# zeitgeist.net
KiCad netlist of a schematic drawn in EAGLE
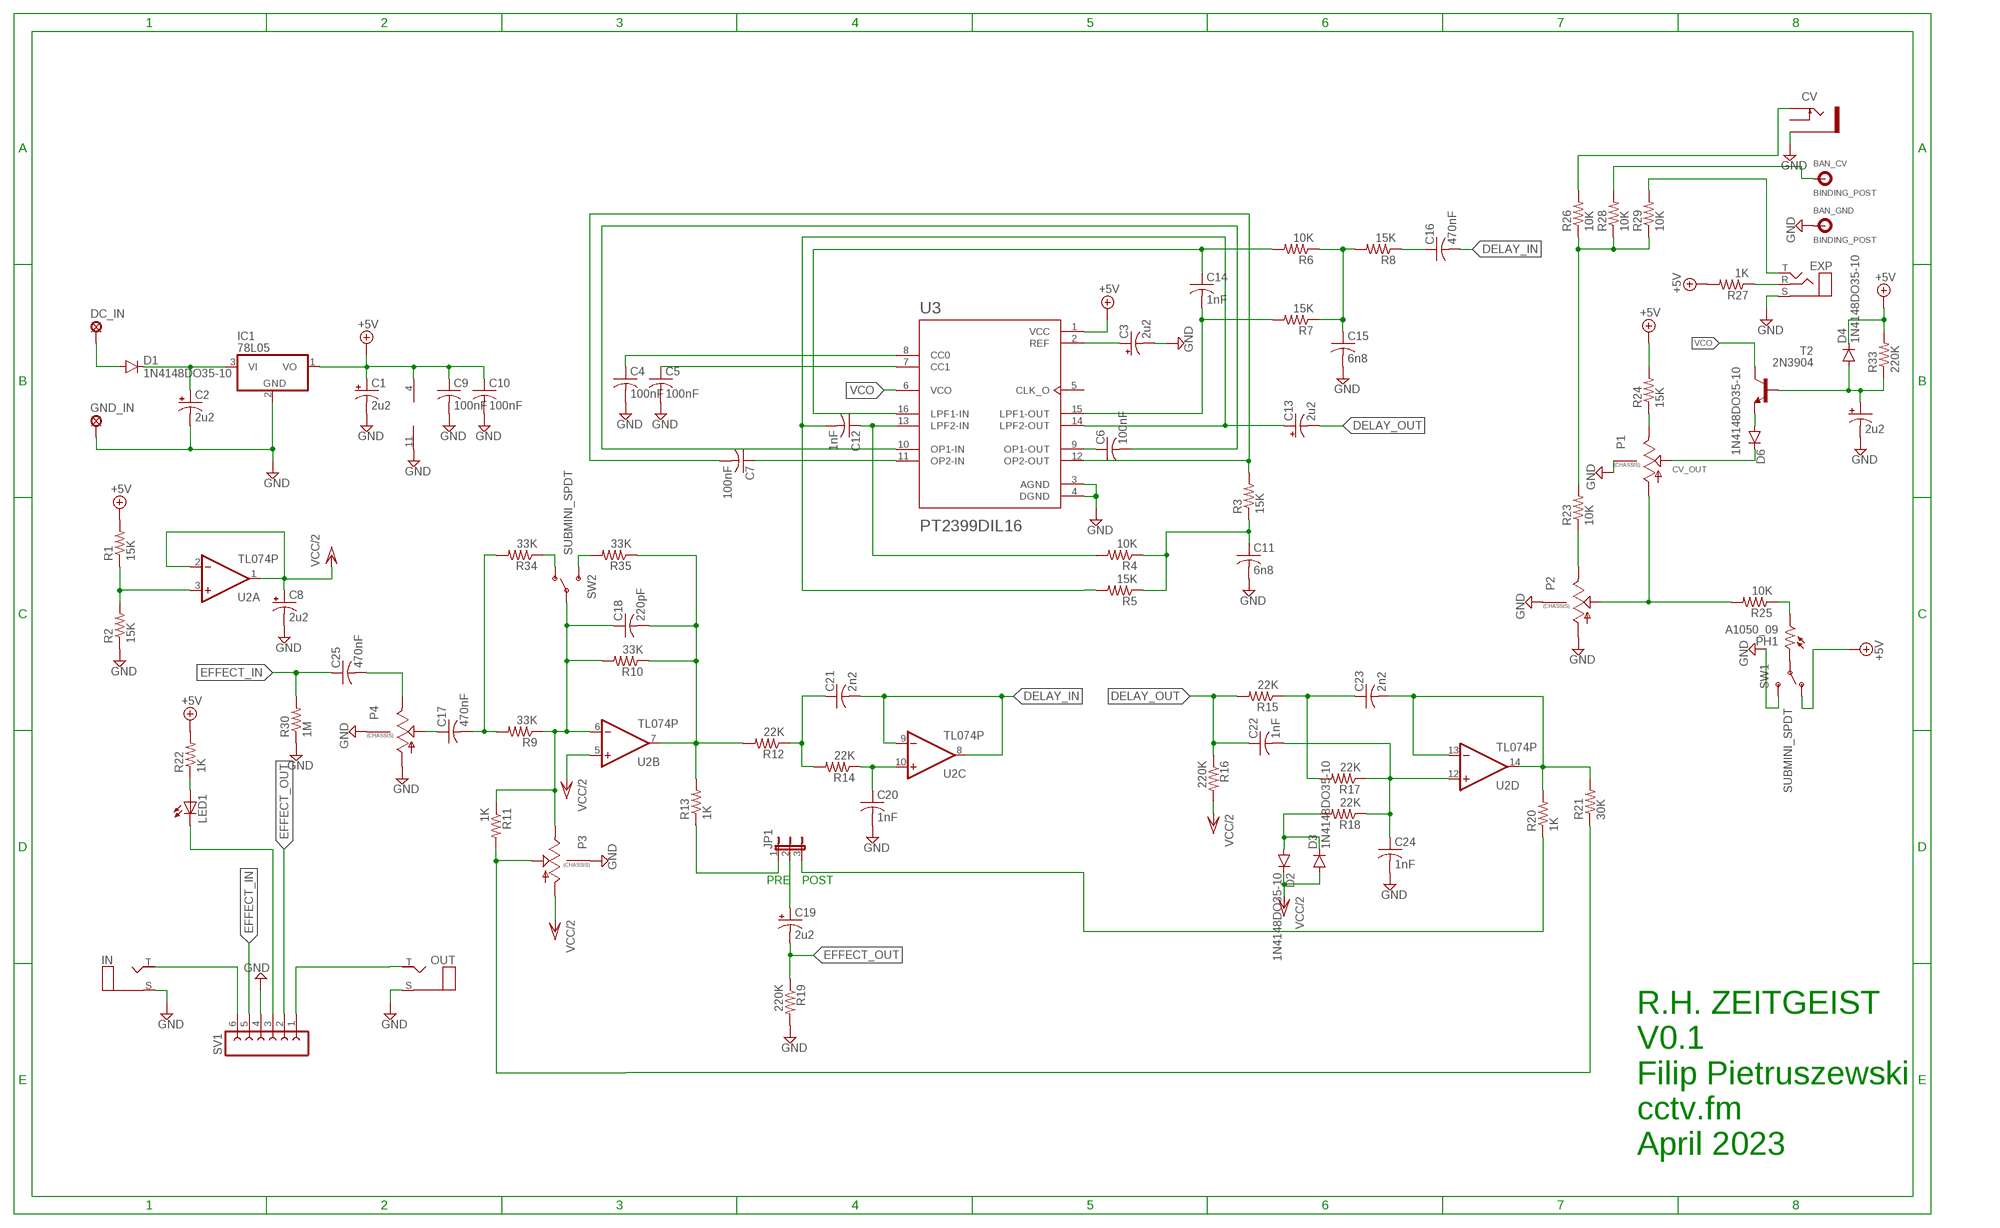
[diagram p0: schematic, sheet 1]

(export (version "E")
  (design (tool "Eeschema 10.0.6"))
  (components
    (comp (ref "BAN_CV")
      (value "BINDING_POST")
      (footprint "eagle-import:BINDING_POST")
      (libsource (lib "eagle-import") (part "BINDING_POST"))
    )
    (comp (ref "BAN_GND")
      (value "BINDING_POST")
      (footprint "eagle-import:BINDING_POST")
      (libsource (lib "eagle-import") (part "BINDING_POST"))
    )
    (comp (ref "C1")
      (value "2u2")
      (footprint "eagle-import:E2,5-6")
      (libsource (lib "eagle-import") (part "CPOL-USE2.5-6"))
    )
    (comp (ref "C2")
      (value "2u2")
      (footprint "eagle-import:E2,5-6")
      (libsource (lib "eagle-import") (part "CPOL-USE2.5-6"))
    )
    (comp (ref "C3")
      (value "2u2")
      (footprint "eagle-import:E2,5-6")
      (libsource (lib "eagle-import") (part "CPOL-USE2.5-6"))
    )
    (comp (ref "C4")
      (value "100nF")
      (footprint "eagle-import:C050-024X044")
      (libsource (lib "eagle-import") (part "C-US050-024X044"))
    )
    (comp (ref "C5")
      (value "100nF")
      (footprint "eagle-import:C050-024X044")
      (libsource (lib "eagle-import") (part "C-US050-024X044"))
    )
    (comp (ref "C6")
      (value "100nF")
      (footprint "eagle-import:C050-035X075")
      (libsource (lib "eagle-import") (part "C-US050-035X075"))
    )
    (comp (ref "C7")
      (value "100nF")
      (footprint "eagle-import:C050-035X075")
      (libsource (lib "eagle-import") (part "C-US050-035X075"))
    )
    (comp (ref "C8")
      (value "2u2")
      (footprint "eagle-import:E2,5-6")
      (libsource (lib "eagle-import") (part "CPOL-USE2.5-6"))
    )
    (comp (ref "C9")
      (value "100nF")
      (footprint "eagle-import:C050-024X044")
      (libsource (lib "eagle-import") (part "C-US050-024X044"))
    )
    (comp (ref "C10")
      (value "100nF")
      (footprint "eagle-import:C050-024X044")
      (libsource (lib "eagle-import") (part "C-US050-024X044"))
    )
    (comp (ref "C11")
      (value "6n8")
      (footprint "eagle-import:C050-035X075")
      (libsource (lib "eagle-import") (part "C-US050-035X075"))
    )
    (comp (ref "C12")
      (value "1nF")
      (footprint "eagle-import:C050-035X075")
      (libsource (lib "eagle-import") (part "C-US050-035X075"))
    )
    (comp (ref "C13")
      (value "2u2")
      (footprint "eagle-import:E2,5-6")
      (libsource (lib "eagle-import") (part "CPOL-USE2.5-6"))
    )
    (comp (ref "C14")
      (value "1nF")
      (footprint "eagle-import:C050-035X075")
      (libsource (lib "eagle-import") (part "C-US050-035X075"))
    )
    (comp (ref "C15")
      (value "6n8")
      (footprint "eagle-import:C050-035X075")
      (libsource (lib "eagle-import") (part "C-US050-035X075"))
    )
    (comp (ref "C16")
      (value "470nF")
      (footprint "eagle-import:C050-035X075")
      (libsource (lib "eagle-import") (part "C-US050-035X075"))
    )
    (comp (ref "C17")
      (value "470nF")
      (footprint "eagle-import:C050-035X075")
      (libsource (lib "eagle-import") (part "C-US050-035X075"))
    )
    (comp (ref "C18")
      (value "220pF")
      (footprint "eagle-import:C050-035X075")
      (libsource (lib "eagle-import") (part "C-US050-035X075"))
    )
    (comp (ref "C19")
      (value "2u2")
      (footprint "eagle-import:E2,5-6")
      (libsource (lib "eagle-import") (part "CPOL-USE2.5-6"))
    )
    (comp (ref "C20")
      (value "1nF")
      (footprint "eagle-import:C050-035X075")
      (libsource (lib "eagle-import") (part "C-US050-035X075"))
    )
    (comp (ref "C21")
      (value "2n2")
      (footprint "eagle-import:C050-035X075")
      (libsource (lib "eagle-import") (part "C-US050-035X075"))
    )
    (comp (ref "C22")
      (value "1nF")
      (footprint "eagle-import:C050-035X075")
      (libsource (lib "eagle-import") (part "C-US050-035X075"))
    )
    (comp (ref "C23")
      (value "2n2")
      (footprint "eagle-import:C050-035X075")
      (libsource (lib "eagle-import") (part "C-US050-035X075"))
    )
    (comp (ref "C24")
      (value "1nF")
      (footprint "eagle-import:C050-035X075")
      (libsource (lib "eagle-import") (part "C-US050-035X075"))
    )
    (comp (ref "C25")
      (value "470nF")
      (footprint "eagle-import:C050-035X075")
      (libsource (lib "eagle-import") (part "C-US050-035X075"))
    )
    (comp (ref "C26")
      (value "2u2")
      (footprint "eagle-import:E2,5-6")
      (libsource (lib "eagle-import") (part "CPOL-USE2.5-6"))
    )
    (comp (ref "CV")
      (value "THONKICONNNEW")
      (footprint "eagle-import:WQP-PJ301M-12_JACK")
      (libsource (lib "eagle-import") (part "THONKICONNNEW"))
    )
    (comp (ref "D1")
      (value "1N4148DO35-10")
      (footprint "eagle-import:DO35-10")
      (libsource (lib "eagle-import") (part "1N4148DO35-10"))
    )
    (comp (ref "D2")
      (value "1N4148DO35-10")
      (footprint "eagle-import:DO35-10")
      (libsource (lib "eagle-import") (part "1N4148DO35-10"))
    )
    (comp (ref "D3")
      (value "1N4148DO35-10")
      (footprint "eagle-import:DO35-10")
      (libsource (lib "eagle-import") (part "1N4148DO35-10"))
    )
    (comp (ref "D4")
      (value "1N4148DO35-10")
      (footprint "eagle-import:DO35-10")
      (libsource (lib "eagle-import") (part "1N4148DO35-10"))
    )
    (comp (ref "D6")
      (value "1N4148DO35-10")
      (footprint "eagle-import:DO35-10")
      (libsource (lib "eagle-import") (part "1N4148DO35-10"))
    )
    (comp (ref "DC_IN")
      (value "SE14")
      (footprint "eagle-import:SE14")
      (libsource (lib "eagle-import") (part "SE14"))
    )
    (comp (ref "EXP")
      (value "STEREO_PADS")
      (footprint "eagle-import:3PADS")
      (libsource (lib "eagle-import") (part "STEREO_PADS"))
    )
    (comp (ref "GND_IN")
      (value "SE14")
      (footprint "eagle-import:SE14")
      (libsource (lib "eagle-import") (part "SE14"))
    )
    (comp (ref "IC1")
      (value "78L05")
      (footprint "eagle-import:TO92")
      (libsource (lib "eagle-import") (part "78ZL05"))
    )
    (comp (ref "IN")
      (value "MONO_PADS")
      (footprint "eagle-import:2PADS")
      (libsource (lib "eagle-import") (part "MONO_PADS"))
    )
    (comp (ref "JP1")
      (value "JP2E")
      (footprint "eagle-import:JP2")
      (libsource (lib "eagle-import") (part "JP2E"))
    )
    (comp (ref "LED1")
      (value "LED5MM")
      (footprint "eagle-import:LED5MM")
      (libsource (lib "eagle-import") (part "LED5MM"))
    )
    (comp (ref "OUT")
      (value "MONO_PADS")
      (footprint "eagle-import:2PADS")
      (libsource (lib "eagle-import") (part "MONO_PADS"))
    )
    (comp (ref "P1")
      (value "9MM_SNAP-IN_POT_CHASSIS")
      (footprint "eagle-import:9MM_SNAP-IN_POT")
      (libsource (lib "eagle-import") (part "9MM_SNAP-IN_POT_CHASSIS"))
    )
    (comp (ref "P2")
      (value "9MM_SNAP-IN_POT_CHASSIS")
      (footprint "eagle-import:9MM_SNAP-IN_POT")
      (libsource (lib "eagle-import") (part "9MM_SNAP-IN_POT_CHASSIS"))
    )
    (comp (ref "P3")
      (value "9MM_SNAP-IN_POT_CHASSIS")
      (footprint "eagle-import:9MM_SNAP-IN_POT")
      (libsource (lib "eagle-import") (part "9MM_SNAP-IN_POT_CHASSIS"))
    )
    (comp (ref "P4")
      (value "9MM_SNAP-IN_POT_CHASSIS")
      (footprint "eagle-import:9MM_SNAP-IN_POT")
      (libsource (lib "eagle-import") (part "9MM_SNAP-IN_POT_CHASSIS"))
    )
    (comp (ref "PH1")
      (value "A1050_09")
      (footprint "eagle-import:T0-46-A10XX")
      (libsource (lib "eagle-import") (part "A1050_09"))
    )
    (comp (ref "R1")
      (value "15K")
      (footprint "eagle-import:0204_7")
      (libsource (lib "eagle-import") (part "RES-7.5-EASYSOLDER"))
    )
    (comp (ref "R2")
      (value "15K")
      (footprint "eagle-import:0204_7")
      (libsource (lib "eagle-import") (part "RES-7.5-EASYSOLDER"))
    )
    (comp (ref "R3")
      (value "15K")
      (footprint "eagle-import:0204_7")
      (libsource (lib "eagle-import") (part "RES-7.5-EASYSOLDER"))
    )
    (comp (ref "R4")
      (value "10K")
      (footprint "eagle-import:0204_7")
      (libsource (lib "eagle-import") (part "RES-7.5-EASYSOLDER"))
    )
    (comp (ref "R5")
      (value "15K")
      (footprint "eagle-import:0204_7")
      (libsource (lib "eagle-import") (part "RES-7.5-EASYSOLDER"))
    )
    (comp (ref "R6")
      (value "10K")
      (footprint "eagle-import:0204_7")
      (libsource (lib "eagle-import") (part "RES-7.5-EASYSOLDER"))
    )
    (comp (ref "R7")
      (value "15K")
      (footprint "eagle-import:0204_7")
      (libsource (lib "eagle-import") (part "RES-7.5-EASYSOLDER"))
    )
    (comp (ref "R8")
      (value "15K")
      (footprint "eagle-import:0204_7")
      (libsource (lib "eagle-import") (part "RES-7.5-EASYSOLDER"))
    )
    (comp (ref "R9")
      (value "33K")
      (footprint "eagle-import:0204_7")
      (libsource (lib "eagle-import") (part "RES-7.5-EASYSOLDER"))
    )
    (comp (ref "R10")
      (value "33K")
      (footprint "eagle-import:0204_7")
      (libsource (lib "eagle-import") (part "RES-7.5-EASYSOLDER"))
    )
    (comp (ref "R11")
      (value "1K")
      (footprint "eagle-import:0204_7")
      (libsource (lib "eagle-import") (part "RES-7.5-EASYSOLDER"))
    )
    (comp (ref "R12")
      (value "22K")
      (footprint "eagle-import:0204_7")
      (libsource (lib "eagle-import") (part "RES-7.5-EASYSOLDER"))
    )
    (comp (ref "R13")
      (value "1K")
      (footprint "eagle-import:0204_7")
      (libsource (lib "eagle-import") (part "RES-7.5-EASYSOLDER"))
    )
    (comp (ref "R14")
      (value "22K")
      (footprint "eagle-import:0204_7")
      (libsource (lib "eagle-import") (part "RES-7.5-EASYSOLDER"))
    )
    (comp (ref "R15")
      (value "22K")
      (footprint "eagle-import:0204_7")
      (libsource (lib "eagle-import") (part "RES-7.5-EASYSOLDER"))
    )
    (comp (ref "R16")
      (value "220K")
      (footprint "eagle-import:0204_7")
      (libsource (lib "eagle-import") (part "RES-7.5-EASYSOLDER"))
    )
    (comp (ref "R17")
      (value "22K")
      (footprint "eagle-import:0204_7")
      (libsource (lib "eagle-import") (part "RES-7.5-EASYSOLDER"))
    )
    (comp (ref "R18")
      (value "22K")
      (footprint "eagle-import:0204_7")
      (libsource (lib "eagle-import") (part "RES-7.5-EASYSOLDER"))
    )
    (comp (ref "R19")
      (value "220K")
      (footprint "eagle-import:0204_7")
      (libsource (lib "eagle-import") (part "RES-7.5-EASYSOLDER"))
    )
    (comp (ref "R20")
      (value "1K")
      (footprint "eagle-import:0204_7")
      (libsource (lib "eagle-import") (part "RES-7.5-EASYSOLDER"))
    )
    (comp (ref "R21")
      (value "30K")
      (footprint "eagle-import:0204_7")
      (libsource (lib "eagle-import") (part "RES-7.5-EASYSOLDER"))
    )
    (comp (ref "R22")
      (value "1K")
      (footprint "eagle-import:0204_7")
      (libsource (lib "eagle-import") (part "RES-7.5-EASYSOLDER"))
    )
    (comp (ref "R23")
      (value "10K")
      (footprint "eagle-import:0204_7")
      (libsource (lib "eagle-import") (part "RES-7.5-EASYSOLDER"))
    )
    (comp (ref "R24")
      (value "15K")
      (footprint "eagle-import:0204_7")
      (libsource (lib "eagle-import") (part "RES-7.5-EASYSOLDER"))
    )
    (comp (ref "R25")
      (value "10K")
      (footprint "eagle-import:0204_7")
      (libsource (lib "eagle-import") (part "RES-7.5-EASYSOLDER"))
    )
    (comp (ref "R26")
      (value "10K")
      (footprint "eagle-import:0204_7")
      (libsource (lib "eagle-import") (part "RES-7.5-EASYSOLDER"))
    )
    (comp (ref "R27")
      (value "1K")
      (footprint "eagle-import:0204_7")
      (libsource (lib "eagle-import") (part "RES-7.5-EASYSOLDER"))
    )
    (comp (ref "R28")
      (value "10K")
      (footprint "eagle-import:0204_7")
      (libsource (lib "eagle-import") (part "RES-7.5-EASYSOLDER"))
    )
    (comp (ref "R29")
      (value "10K")
      (footprint "eagle-import:0204_7")
      (libsource (lib "eagle-import") (part "RES-7.5-EASYSOLDER"))
    )
    (comp (ref "R30")
      (value "1M")
      (footprint "eagle-import:0204_7")
      (libsource (lib "eagle-import") (part "RES-7.5-EASYSOLDER"))
    )
    (comp (ref "R33")
      (value "220K")
      (footprint "eagle-import:0204_7")
      (libsource (lib "eagle-import") (part "RES-7.5-EASYSOLDER"))
    )
    (comp (ref "R34")
      (value "33K")
      (footprint "eagle-import:0204_7")
      (libsource (lib "eagle-import") (part "RES-7.5-EASYSOLDER"))
    )
    (comp (ref "R35")
      (value "33K")
      (footprint "eagle-import:0204_7")
      (libsource (lib "eagle-import") (part "RES-7.5-EASYSOLDER"))
    )
    (comp (ref "SV1")
      (value "FE06-1")
      (footprint "eagle-import:FE06")
      (libsource (lib "eagle-import") (part "FE06-1"))
    )
    (comp (ref "SW1")
      (value "SUBMINI_SPDT")
      (footprint "eagle-import:SUBMINI_TOGGLE")
      (libsource (lib "eagle-import") (part "SUBMINI_SPDT"))
    )
    (comp (ref "SW2")
      (value "SUBMINI_SPDT")
      (footprint "eagle-import:SUBMINI_TOGGLE")
      (libsource (lib "eagle-import") (part "SUBMINI_SPDT"))
    )
    (comp (ref "T2")
      (value "2N3904")
      (footprint "eagle-import:TO92")
      (libsource (lib "eagle-import") (part "2N3904"))
    )
    (comp (ref "U2")
      (value "TL074P")
      (footprint "eagle-import:DIL14")
      (libsource (lib "eagle-import") (part "TL074P"))
    )
    (comp (ref "U3")
      (value "PT2399DIL16")
      (footprint "eagle-import:DIL16")
      (libsource (lib "eagle-import") (part "PT2399DIL16"))
    )
  )
  (nets
    (net (code "1") (name "+5V") (class "Default")
      (node (ref "C1") (pin "+") (pinfunction "+_+") (pintype "passive"))
      (node (ref "C10") (pin "1") (pinfunction "1_1") (pintype "passive"))
      (node (ref "C9") (pin "1") (pinfunction "1_1") (pintype "passive"))
      (node (ref "D4") (pin "C") (pinfunction "C_C") (pintype "passive"))
      (node (ref "IC1") (pin "1") (pinfunction "VO_1") (pintype "passive"))
      (node (ref "R1") (pin "2") (pinfunction "2_2") (pintype "passive"))
      (node (ref "R22") (pin "2") (pinfunction "2_2") (pintype "passive"))
      (node (ref "R24") (pin "2") (pinfunction "2_2") (pintype "passive"))
      (node (ref "R27") (pin "2") (pinfunction "2_2") (pintype "passive"))
      (node (ref "R33") (pin "2") (pinfunction "2_2") (pintype "passive"))
      (node (ref "SW1") (pin "1") (pinfunction "O_1") (pintype "passive"))
      (node (ref "U2") (pin "4") (pinfunction "V+_4") (pintype "power_in"))
      (node (ref "U3") (pin "1") (pinfunction "VCC_1") (pintype "power_in"))
    )
    (net (code "2") (name "/CV_OUT") (class "Default")
      (node (ref "D6") (pin "C") (pinfunction "C_C") (pintype "passive"))
      (node (ref "P1") (pin "2") (pinfunction "S_2") (pintype "passive"))
    )
    (net (code "3") (name "DELAY_IN") (class "Default")
      (node (ref "C16") (pin "2") (pinfunction "2_2") (pintype "passive"))
      (node (ref "C21") (pin "2") (pinfunction "2_2") (pintype "passive"))
      (node (ref "U2") (pin "8") (pinfunction "OUT_8") (pintype "output"))
      (node (ref "U2") (pin "9") (pinfunction "-IN_9") (pintype "input"))
    )
    (net (code "4") (name "DELAY_OUT") (class "Default")
      (node (ref "C13") (pin "-") (pinfunction "-_-") (pintype "passive"))
      (node (ref "C22") (pin "1") (pinfunction "1_1") (pintype "passive"))
      (node (ref "R15") (pin "2") (pinfunction "2_2") (pintype "passive"))
      (node (ref "R16") (pin "1") (pinfunction "1_1") (pintype "passive"))
    )
    (net (code "5") (name "EFFECT_IN") (class "Default")
      (node (ref "C25") (pin "1") (pinfunction "1_1") (pintype "passive"))
      (node (ref "R30") (pin "2") (pinfunction "2_2") (pintype "passive"))
      (node (ref "SV1") (pin "5") (pinfunction "5_5") (pintype "passive"))
    )
    (net (code "6") (name "EFFECT_OUT") (class "Default")
      (node (ref "C19") (pin "-") (pinfunction "-_-") (pintype "passive"))
      (node (ref "R19") (pin "1") (pinfunction "1_1") (pintype "passive"))
      (node (ref "SV1") (pin "2") (pinfunction "2_2") (pintype "passive"))
    )
    (net (code "7") (name "GND") (class "Default")
      (node (ref "BAN_GND") (pin "P$1") (pinfunction "P$1_P$1") (pintype "bidirectional"))
      (node (ref "C1") (pin "-") (pinfunction "-_-") (pintype "passive"))
      (node (ref "C10") (pin "2") (pinfunction "2_2") (pintype "passive"))
      (node (ref "C11") (pin "2") (pinfunction "2_2") (pintype "passive"))
      (node (ref "C15") (pin "2") (pinfunction "2_2") (pintype "passive"))
      (node (ref "C2") (pin "-") (pinfunction "-_-") (pintype "passive"))
      (node (ref "C20") (pin "2") (pinfunction "2_2") (pintype "passive"))
      (node (ref "C24") (pin "2") (pinfunction "2_2") (pintype "passive"))
      (node (ref "C26") (pin "-") (pinfunction "-_-") (pintype "passive"))
      (node (ref "C3") (pin "-") (pinfunction "-_-") (pintype "passive"))
      (node (ref "C4") (pin "2") (pinfunction "2_2") (pintype "passive"))
      (node (ref "C5") (pin "2") (pinfunction "2_2") (pintype "passive"))
      (node (ref "C8") (pin "-") (pinfunction "-_-") (pintype "passive"))
      (node (ref "C9") (pin "2") (pinfunction "2_2") (pintype "passive"))
      (node (ref "CV") (pin "P$3_SLEEVE") (pinfunction "SLEEVE_P$3_SLEEVE") (pintype "passive"))
      (node (ref "EXP") (pin "S") (pinfunction "S_S") (pintype "passive"))
      (node (ref "GND_IN") (pin "MP") (pinfunction "MP_MP") (pintype "passive"))
      (node (ref "IC1") (pin "2") (pinfunction "GND_2") (pintype "passive"))
      (node (ref "IN") (pin "S") (pinfunction "S_S") (pintype "passive"))
      (node (ref "OUT") (pin "S") (pinfunction "S_S") (pintype "passive"))
      (node (ref "P1") (pin "CHASSIS1") (pinfunction "P$1_CHASSIS1") (pintype "passive"))
      (node (ref "P1") (pin "CHASSIS2") (pinfunction "P$1_CHASSIS2") (pintype "passive"))
      (node (ref "P2") (pin "1") (pinfunction "A_1") (pintype "passive"))
      (node (ref "P2") (pin "CHASSIS1") (pinfunction "P$1_CHASSIS1") (pintype "passive"))
      (node (ref "P2") (pin "CHASSIS2") (pinfunction "P$1_CHASSIS2") (pintype "passive"))
      (node (ref "P3") (pin "CHASSIS1") (pinfunction "P$1_CHASSIS1") (pintype "passive"))
      (node (ref "P3") (pin "CHASSIS2") (pinfunction "P$1_CHASSIS2") (pintype "passive"))
      (node (ref "P4") (pin "1") (pinfunction "A_1") (pintype "passive"))
      (node (ref "P4") (pin "CHASSIS1") (pinfunction "P$1_CHASSIS1") (pintype "passive"))
      (node (ref "P4") (pin "CHASSIS2") (pinfunction "P$1_CHASSIS2") (pintype "passive"))
      (node (ref "R19") (pin "2") (pinfunction "2_2") (pintype "passive"))
      (node (ref "R2") (pin "1") (pinfunction "1_1") (pintype "passive"))
      (node (ref "R30") (pin "1") (pinfunction "1_1") (pintype "passive"))
      (node (ref "SV1") (pin "4") (pinfunction "4_4") (pintype "passive"))
      (node (ref "SW1") (pin "3") (pinfunction "S_3") (pintype "passive"))
      (node (ref "U2") (pin "11") (pinfunction "V-_11") (pintype "power_in"))
      (node (ref "U3") (pin "3") (pinfunction "AGND_3") (pintype "power_in"))
      (node (ref "U3") (pin "4") (pinfunction "DGND_4") (pintype "power_in"))
    )
    (net (code "8") (name "Net-(BAN_CV-PadP$1)") (class "Default")
      (node (ref "BAN_CV") (pin "P$1") (pinfunction "P$1_P$1") (pintype "bidirectional"))
      (node (ref "R28") (pin "2") (pinfunction "2_2") (pintype "passive"))
    )
    (net (code "9") (name "Net-(C11-Pad1)") (class "Default")
      (node (ref "C11") (pin "1") (pinfunction "1_1") (pintype "passive"))
      (node (ref "R3") (pin "1") (pinfunction "1_1") (pintype "passive"))
      (node (ref "R4") (pin "1") (pinfunction "1_1") (pintype "passive"))
      (node (ref "R5") (pin "1") (pinfunction "1_1") (pintype "passive"))
    )
    (net (code "10") (name "Net-(C15-Pad1)") (class "Default")
      (node (ref "C15") (pin "1") (pinfunction "1_1") (pintype "passive"))
      (node (ref "R6") (pin "1") (pinfunction "1_1") (pintype "passive"))
      (node (ref "R7") (pin "1") (pinfunction "1_1") (pintype "passive"))
      (node (ref "R8") (pin "2") (pinfunction "2_2") (pintype "passive"))
    )
    (net (code "11") (name "Net-(C16-Pad1)") (class "Default")
      (node (ref "C16") (pin "1") (pinfunction "1_1") (pintype "passive"))
      (node (ref "R8") (pin "1") (pinfunction "1_1") (pintype "passive"))
    )
    (net (code "12") (name "Net-(C17-Pad2)") (class "Default")
      (node (ref "C17") (pin "2") (pinfunction "2_2") (pintype "passive"))
      (node (ref "R34") (pin "2") (pinfunction "2_2") (pintype "passive"))
      (node (ref "R9") (pin "2") (pinfunction "2_2") (pintype "passive"))
    )
    (net (code "13") (name "Net-(C19-Pad+)") (class "Default")
      (node (ref "C19") (pin "+") (pinfunction "+_+") (pintype "passive"))
      (node (ref "JP1") (pin "2") (pinfunction "2_2") (pintype "passive"))
    )
    (net (code "14") (name "Net-(C21-Pad1)") (class "Default")
      (node (ref "C21") (pin "1") (pinfunction "1_1") (pintype "passive"))
      (node (ref "R12") (pin "1") (pinfunction "1_1") (pintype "passive"))
      (node (ref "R14") (pin "2") (pinfunction "2_2") (pintype "passive"))
    )
    (net (code "15") (name "Net-(C23-Pad1)") (class "Default")
      (node (ref "C23") (pin "1") (pinfunction "1_1") (pintype "passive"))
      (node (ref "R15") (pin "1") (pinfunction "1_1") (pintype "passive"))
      (node (ref "R17") (pin "2") (pinfunction "2_2") (pintype "passive"))
    )
    (net (code "16") (name "Net-(CV-TIP)") (class "Default")
      (node (ref "CV") (pin "P$1_TIP") (pinfunction "TIP_P$1_TIP") (pintype "passive"))
      (node (ref "R26") (pin "2") (pinfunction "2_2") (pintype "passive"))
    )
    (net (code "17") (name "Net-(D1-PadA)") (class "Default")
      (node (ref "D1") (pin "A") (pinfunction "A_A") (pintype "passive"))
      (node (ref "DC_IN") (pin "MP") (pinfunction "MP_MP") (pintype "passive"))
    )
    (net (code "18") (name "Net-(D2-PadA)") (class "Default")
      (node (ref "D2") (pin "A") (pinfunction "A_A") (pintype "passive"))
      (node (ref "D3") (pin "C") (pinfunction "C_C") (pintype "passive"))
      (node (ref "R18") (pin "2") (pinfunction "2_2") (pintype "passive"))
    )
    (net (code "19") (name "Net-(EXP-PadR)") (class "Default")
      (node (ref "EXP") (pin "R") (pinfunction "R_R") (pintype "passive"))
      (node (ref "R27") (pin "1") (pinfunction "1_1") (pintype "passive"))
    )
    (net (code "20") (name "Net-(EXP-PadT)") (class "Default")
      (node (ref "EXP") (pin "T") (pinfunction "T_T") (pintype "passive"))
      (node (ref "R29") (pin "2") (pinfunction "2_2") (pintype "passive"))
    )
    (net (code "21") (name "Net-(IC1-VI)") (class "Default")
      (node (ref "C2") (pin "+") (pinfunction "+_+") (pintype "passive"))
      (node (ref "D1") (pin "C") (pinfunction "C_C") (pintype "passive"))
      (node (ref "IC1") (pin "3") (pinfunction "VI_3") (pintype "input"))
    )
    (net (code "22") (name "Net-(IN-PadT)") (class "Default")
      (node (ref "IN") (pin "T") (pinfunction "T_T") (pintype "passive"))
      (node (ref "SV1") (pin "6") (pinfunction "6_6") (pintype "passive"))
    )
    (net (code "23") (name "Net-(JP1-Pad1)") (class "Default")
      (node (ref "JP1") (pin "1") (pinfunction "1_1") (pintype "passive"))
      (node (ref "R13") (pin "1") (pinfunction "1_1") (pintype "passive"))
    )
    (net (code "24") (name "Net-(JP1-Pad3)") (class "Default")
      (node (ref "JP1") (pin "3") (pinfunction "3_3") (pintype "passive"))
      (node (ref "R20") (pin "1") (pinfunction "1_1") (pintype "passive"))
    )
    (net (code "25") (name "Net-(LED1-C)") (class "Default")
      (node (ref "LED1") (pin "K") (pinfunction "C_K") (pintype "passive"))
      (node (ref "SV1") (pin "3") (pinfunction "3_3") (pintype "passive"))
    )
    (net (code "26") (name "Net-(LED1-PadA)") (class "Default")
      (node (ref "LED1") (pin "A") (pinfunction "A_A") (pintype "passive"))
      (node (ref "R22") (pin "1") (pinfunction "1_1") (pintype "passive"))
    )
    (net (code "27") (name "Net-(OUT-PadT)") (class "Default")
      (node (ref "OUT") (pin "T") (pinfunction "T_T") (pintype "passive"))
      (node (ref "SV1") (pin "1") (pinfunction "1_1") (pintype "passive"))
    )
    (net (code "28") (name "Net-(P1-A)") (class "Default")
      (node (ref "P1") (pin "1") (pinfunction "A_1") (pintype "passive"))
      (node (ref "P2") (pin "2") (pinfunction "S_2") (pintype "passive"))
      (node (ref "R25") (pin "2") (pinfunction "2_2") (pintype "passive"))
    )
    (net (code "29") (name "Net-(P1-E)") (class "Default")
      (node (ref "P1") (pin "3") (pinfunction "E_3") (pintype "passive"))
      (node (ref "R24") (pin "1") (pinfunction "1_1") (pintype "passive"))
    )
    (net (code "30") (name "Net-(P2-E)") (class "Default")
      (node (ref "P2") (pin "3") (pinfunction "E_3") (pintype "passive"))
      (node (ref "R23") (pin "1") (pinfunction "1_1") (pintype "passive"))
    )
    (net (code "31") (name "Net-(P3-E)") (class "Default")
      (node (ref "C18") (pin "1") (pinfunction "1_1") (pintype "passive"))
      (node (ref "P3") (pin "3") (pinfunction "E_3") (pintype "passive"))
      (node (ref "R10") (pin "2") (pinfunction "2_2") (pintype "passive"))
      (node (ref "R11") (pin "1") (pinfunction "1_1") (pintype "passive"))
      (node (ref "R9") (pin "1") (pinfunction "1_1") (pintype "passive"))
      (node (ref "SW2") (pin "COM") (pinfunction "COMMON_COM") (pintype "passive"))
      (node (ref "U2") (pin "6") (pinfunction "-IN_6") (pintype "input"))
    )
    (net (code "32") (name "Net-(P3-S)") (class "Default")
      (node (ref "P3") (pin "2") (pinfunction "S_2") (pintype "passive"))
      (node (ref "R11") (pin "2") (pinfunction "2_2") (pintype "passive"))
      (node (ref "R21") (pin "1") (pinfunction "1_1") (pintype "passive"))
    )
    (net (code "33") (name "Net-(P4-E)") (class "Default")
      (node (ref "C25") (pin "2") (pinfunction "2_2") (pintype "passive"))
      (node (ref "P4") (pin "3") (pinfunction "E_3") (pintype "passive"))
    )
    (net (code "34") (name "Net-(P4-S)") (class "Default")
      (node (ref "C17") (pin "1") (pinfunction "1_1") (pintype "passive"))
      (node (ref "P4") (pin "2") (pinfunction "S_2") (pintype "passive"))
    )
    (net (code "35") (name "Net-(PH1-Pad2)") (class "Default")
      (node (ref "PH1") (pin "2") (pinfunction "2_2") (pintype "passive"))
      (node (ref "R25") (pin "1") (pinfunction "1_1") (pintype "passive"))
    )
    (net (code "36") (name "Net-(R23-Pad2)") (class "Default")
      (node (ref "R23") (pin "2") (pinfunction "2_2") (pintype "passive"))
      (node (ref "R26") (pin "1") (pinfunction "1_1") (pintype "passive"))
      (node (ref "R28") (pin "1") (pinfunction "1_1") (pintype "passive"))
      (node (ref "R29") (pin "1") (pinfunction "1_1") (pintype "passive"))
    )
    (net (code "37") (name "Net-(SW1-COMMON)") (class "Default")
      (node (ref "PH1") (pin "1") (pinfunction "1_1") (pintype "passive"))
      (node (ref "SW1") (pin "COM") (pinfunction "COMMON_COM") (pintype "passive"))
    )
    (net (code "38") (name "Net-(SW2-O)") (class "Default")
      (node (ref "R34") (pin "1") (pinfunction "1_1") (pintype "passive"))
      (node (ref "SW2") (pin "1") (pinfunction "O_1") (pintype "passive"))
    )
    (net (code "39") (name "Net-(SW2-S)") (class "Default")
      (node (ref "R35") (pin "2") (pinfunction "2_2") (pintype "passive"))
      (node (ref "SW2") (pin "3") (pinfunction "S_3") (pintype "passive"))
    )
    (net (code "40") (name "Net-(T2-B)") (class "Default")
      (node (ref "C26") (pin "+") (pinfunction "+_+") (pintype "passive"))
      (node (ref "D4") (pin "A") (pinfunction "A_A") (pintype "passive"))
      (node (ref "R33") (pin "1") (pinfunction "1_1") (pintype "passive"))
      (node (ref "T2") (pin "2") (pinfunction "B_2") (pintype "passive"))
    )
    (net (code "41") (name "Net-(T2-E)") (class "Default")
      (node (ref "D6") (pin "A") (pinfunction "A_A") (pintype "passive"))
      (node (ref "T2") (pin "3") (pinfunction "E_3") (pintype "passive"))
    )
    (net (code "42") (name "Net-(U2A-+IN)") (class "Default")
      (node (ref "R1") (pin "1") (pinfunction "1_1") (pintype "passive"))
      (node (ref "R2") (pin "2") (pinfunction "2_2") (pintype "passive"))
      (node (ref "U2") (pin "3") (pinfunction "+IN_3") (pintype "input"))
    )
    (net (code "43") (name "Net-(U2B-OUT)") (class "Default")
      (node (ref "C18") (pin "2") (pinfunction "2_2") (pintype "passive"))
      (node (ref "R10") (pin "1") (pinfunction "1_1") (pintype "passive"))
      (node (ref "R12") (pin "2") (pinfunction "2_2") (pintype "passive"))
      (node (ref "R13") (pin "2") (pinfunction "2_2") (pintype "passive"))
      (node (ref "R35") (pin "1") (pinfunction "1_1") (pintype "passive"))
      (node (ref "U2") (pin "7") (pinfunction "OUT_7") (pintype "output"))
    )
    (net (code "44") (name "Net-(U2C-+IN)") (class "Default")
      (node (ref "C20") (pin "1") (pinfunction "1_1") (pintype "passive"))
      (node (ref "R14") (pin "1") (pinfunction "1_1") (pintype "passive"))
      (node (ref "U2") (pin "10") (pinfunction "+IN_10") (pintype "input"))
    )
    (net (code "45") (name "Net-(U2D-+IN)") (class "Default")
      (node (ref "C22") (pin "2") (pinfunction "2_2") (pintype "passive"))
      (node (ref "C24") (pin "1") (pinfunction "1_1") (pintype "passive"))
      (node (ref "R17") (pin "1") (pinfunction "1_1") (pintype "passive"))
      (node (ref "R18") (pin "1") (pinfunction "1_1") (pintype "passive"))
      (node (ref "U2") (pin "12") (pinfunction "+IN_12") (pintype "input"))
    )
    (net (code "46") (name "Net-(U2D--IN)") (class "Default")
      (node (ref "C23") (pin "2") (pinfunction "2_2") (pintype "passive"))
      (node (ref "R20") (pin "2") (pinfunction "2_2") (pintype "passive"))
      (node (ref "R21") (pin "2") (pinfunction "2_2") (pintype "passive"))
      (node (ref "U2") (pin "13") (pinfunction "-IN_13") (pintype "input"))
      (node (ref "U2") (pin "14") (pinfunction "OUT_14") (pintype "output"))
    )
    (net (code "47") (name "Net-(U3-CC0)") (class "Default")
      (node (ref "C4") (pin "1") (pinfunction "1_1") (pintype "passive"))
      (node (ref "U3") (pin "8") (pinfunction "CC0_8") (pintype "input"))
    )
    (net (code "48") (name "Net-(U3-CC1)") (class "Default")
      (node (ref "C5") (pin "1") (pinfunction "1_1") (pintype "passive"))
      (node (ref "U3") (pin "7") (pinfunction "CC1_7") (pintype "input"))
    )
    (net (code "49") (name "Net-(U3-LPF1-IN)") (class "Default")
      (node (ref "C14") (pin "1") (pinfunction "1_1") (pintype "passive"))
      (node (ref "R6") (pin "2") (pinfunction "2_2") (pintype "passive"))
      (node (ref "U3") (pin "16") (pinfunction "LPF1-IN_16") (pintype "input"))
    )
    (net (code "50") (name "Net-(U3-LPF1-OUT)") (class "Default")
      (node (ref "C14") (pin "2") (pinfunction "2_2") (pintype "passive"))
      (node (ref "R7") (pin "2") (pinfunction "2_2") (pintype "passive"))
      (node (ref "U3") (pin "15") (pinfunction "LPF1-OUT_15") (pintype "output"))
    )
    (net (code "51") (name "Net-(U3-LPF2-IN)") (class "Default")
      (node (ref "C12") (pin "1") (pinfunction "1_1") (pintype "passive"))
      (node (ref "R4") (pin "2") (pinfunction "2_2") (pintype "passive"))
      (node (ref "U3") (pin "13") (pinfunction "LPF2-IN_13") (pintype "input"))
    )
    (net (code "52") (name "Net-(U3-LPF2-OUT)") (class "Default")
      (node (ref "C12") (pin "2") (pinfunction "2_2") (pintype "passive"))
      (node (ref "C13") (pin "+") (pinfunction "+_+") (pintype "passive"))
      (node (ref "R5") (pin "2") (pinfunction "2_2") (pintype "passive"))
      (node (ref "U3") (pin "14") (pinfunction "LPF2-OUT_14") (pintype "output"))
    )
    (net (code "53") (name "Net-(U3-OP1-IN)") (class "Default")
      (node (ref "C6") (pin "2") (pinfunction "2_2") (pintype "passive"))
      (node (ref "U3") (pin "10") (pinfunction "OP1-IN_10") (pintype "input"))
    )
    (net (code "54") (name "Net-(U3-OP1-OUT)") (class "Default")
      (node (ref "C6") (pin "1") (pinfunction "1_1") (pintype "passive"))
      (node (ref "U3") (pin "9") (pinfunction "OP1-OUT_9") (pintype "output"))
    )
    (net (code "55") (name "Net-(U3-OP2-IN)") (class "Default")
      (node (ref "C7") (pin "1") (pinfunction "1_1") (pintype "passive"))
      (node (ref "U3") (pin "11") (pinfunction "OP2-IN_11") (pintype "input"))
    )
    (net (code "56") (name "Net-(U3-OP2-OUT)") (class "Default")
      (node (ref "C7") (pin "2") (pinfunction "2_2") (pintype "passive"))
      (node (ref "R3") (pin "2") (pinfunction "2_2") (pintype "passive"))
      (node (ref "U3") (pin "12") (pinfunction "OP2-OUT_12") (pintype "output"))
    )
    (net (code "57") (name "Net-(U3-REF)") (class "Default")
      (node (ref "C3") (pin "+") (pinfunction "+_+") (pintype "passive"))
      (node (ref "U3") (pin "2") (pinfunction "REF_2") (pintype "power_in"))
    )
    (net (code "58") (name "VCC{slash}2") (class "Default")
      (node (ref "C8") (pin "+") (pinfunction "+_+") (pintype "passive"))
      (node (ref "D2") (pin "C") (pinfunction "C_C") (pintype "passive"))
      (node (ref "D3") (pin "A") (pinfunction "A_A") (pintype "passive"))
      (node (ref "P3") (pin "1") (pinfunction "A_1") (pintype "passive"))
      (node (ref "R16") (pin "2") (pinfunction "2_2") (pintype "passive"))
      (node (ref "U2") (pin "1") (pinfunction "OUT_1") (pintype "output"))
      (node (ref "U2") (pin "2") (pinfunction "-IN_2") (pintype "input"))
      (node (ref "U2") (pin "5") (pinfunction "+IN_5") (pintype "input"))
    )
    (net (code "59") (name "VCO") (class "Default")
      (node (ref "T2") (pin "1") (pinfunction "C_1") (pintype "passive"))
      (node (ref "U3") (pin "6") (pinfunction "VCO_6") (pintype "input"))
    )
    (net (code "60") (name "unconnected-(CV-SWITCH-PadP$2_SWITCH)") (class "Default")
      (node (ref "CV") (pin "P$2_SWITCH") (pinfunction "SWITCH_P$2_SWITCH") (pintype "passive"))
    )
    (net (code "61") (name "unconnected-(U3-CLK_O-Pad5)") (class "Default")
      (node (ref "U3") (pin "5") (pinfunction "CLK_O_5") (pintype "output"))
    )
  )
)
